# RF2401.net
KiCad netlist of a schematic drawn in Altium Designer
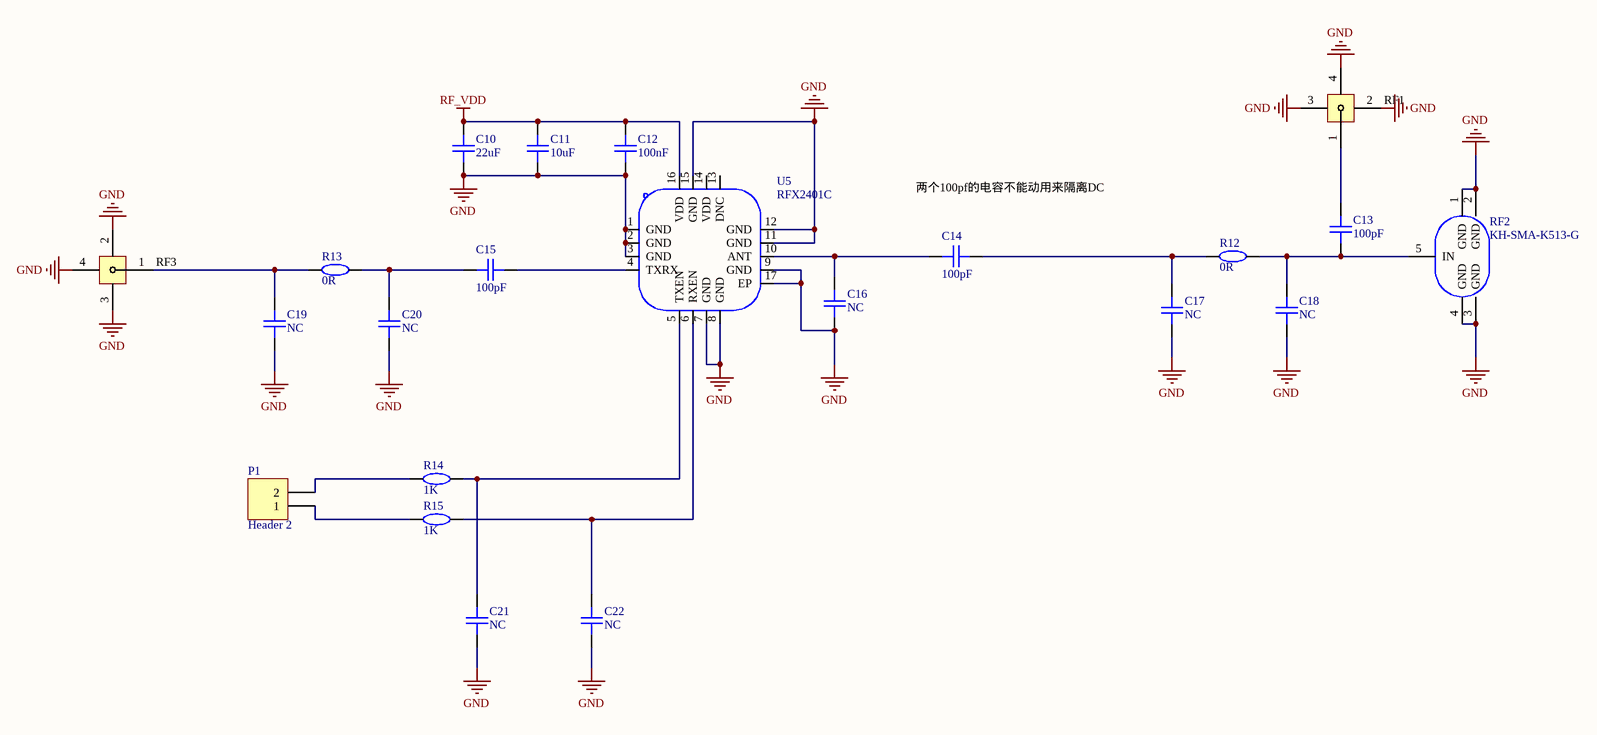
[diagram p0: RF2401.SchDoc]

(export (version "E")
  (design (tool "Eeschema 10.0.6"))
  (components
    (comp (ref "C10")
      (value "22uF")
      (footprint "C0603")
      (fields (field (name "NAME") "22uF"))
      (libsource (lib "my_library") (part "CAP_0603"))
    )
    (comp (ref "C11")
      (value "10uF")
      (footprint "C0603")
      (fields (field (name "NAME") "10uF"))
      (libsource (lib "my_library") (part "CAP_0603"))
    )
    (comp (ref "C12")
      (value "100nF")
      (footprint "C0402")
      (fields (field (name "NAME") "100nF"))
      (libsource (lib "my_library") (part "CAP_0402"))
    )
    (comp (ref "C13")
      (value "100pF")
      (footprint "C0402")
      (fields (field (name "NAME") "100pF"))
      (libsource (lib "my_library") (part "CAP_0402"))
    )
    (comp (ref "C14")
      (value "100pF")
      (footprint "C0402")
      (fields (field (name "NAME") "100pF"))
      (libsource (lib "my_library") (part "CAP_0402"))
    )
    (comp (ref "C15")
      (value "100pF")
      (footprint "C0402")
      (fields (field (name "NAME") "100pF"))
      (libsource (lib "my_library") (part "CAP_0402"))
    )
    (comp (ref "C16")
      (value "NC")
      (footprint "C0402")
      (fields (field (name "NAME") "NC"))
      (libsource (lib "my_library") (part "CAP_0402"))
    )
    (comp (ref "C17")
      (value "NC")
      (footprint "C0402")
      (fields (field (name "NAME") "NC"))
      (libsource (lib "my_library") (part "CAP_0402"))
    )
    (comp (ref "C18")
      (value "NC")
      (footprint "C0402")
      (fields (field (name "NAME") "NC"))
      (libsource (lib "my_library") (part "CAP_0402"))
    )
    (comp (ref "C19")
      (value "NC")
      (footprint "C0402")
      (fields (field (name "NAME") "NC"))
      (libsource (lib "my_library") (part "CAP_0402"))
    )
    (comp (ref "C20")
      (value "NC")
      (footprint "C0402")
      (fields (field (name "NAME") "NC"))
      (libsource (lib "my_library") (part "CAP_0402"))
    )
    (comp (ref "C21")
      (value "NC")
      (footprint "C0402")
      (fields (field (name "NAME") "NC"))
      (libsource (lib "my_library") (part "CAP_0402"))
    )
    (comp (ref "C22")
      (value "NC")
      (footprint "C0402")
      (fields (field (name "NAME") "NC"))
      (libsource (lib "my_library") (part "CAP_0402"))
    )
    (comp (ref "P1")
      (value "Header 2")
      (footprint "HDR1X2")
      (description "Header, 2-Pin")
      (fields (field (name "PUBLISHER") "Altium Limited"))
      (libsource (lib "Miscellaneous Connectors") (part "Header 2"))
    )
    (comp (ref "R12")
      (value "0R")
      (footprint "R0402")
      (fields (field (name "NAME") "0R"))
      (libsource (lib "my_library") (part "Res_0402"))
    )
    (comp (ref "R13")
      (value "0R")
      (footprint "R0402")
      (fields (field (name "NAME") "0R"))
      (libsource (lib "my_library") (part "Res_0402"))
    )
    (comp (ref "R14")
      (value "1K")
      (footprint "R0402")
      (fields (field (name "NAME") "1K"))
      (libsource (lib "my_library") (part "Res_0402"))
    )
    (comp (ref "R15")
      (value "1K")
      (footprint "R0402")
      (fields (field (name "NAME") "1K"))
      (libsource (lib "my_library") (part "Res_0402"))
    )
    (comp (ref "RF1")
      (value "BWIPX-4-001E")
      (footprint "IPEX-SMD_BWIPX-4-001E")
      (description "C784401")
      (fields (field (name "MANUFACTURER") "BAT WIRELESS(蝙蝠无线)"))
      (libsource (lib "my_library") (part "BWIPX-4-001E"))
    )
    (comp (ref "RF2")
      (value "KH-SMA-K513-G")
      (footprint "ANT-TH_KH-SMA-K513-G")
      (fields (field (name "MANUFACTURER") "kinghelm(金航标)") (field (name "NAME") "KH-SMA-K513-G"))
      (libsource (lib "my_library") (part "KH-SMA-K513-G"))
    )
    (comp (ref "RF3")
      (value "BWIPX-4-001E")
      (footprint "IPEX-SMD_BWIPX-4-001E")
      (description "C784401")
      (fields (field (name "MANUFACTURER") "BAT WIRELESS(蝙蝠无线)"))
      (libsource (lib "") (part "BWIPX-4-001E_1"))
    )
    (comp (ref "U5")
      (value "RFX2401C")
      (footprint "QFN-16_L3.0-W3.0-P0.50-BL-EP1.7")
      (fields (field (name "MANUFACTURER") "SKYWORKS") (field (name "NAME") "RFX2401C"))
      (libsource (lib "my_library") (part "RFX2401C"))
    )
  )
  (nets
    (net (code "1") (name "GND") (class "Default")
      (node (ref "C10") (pin "1") (pinfunction "1_1") (pintype "passive"))
      (node (ref "C11") (pin "1") (pinfunction "1_1") (pintype "passive"))
      (node (ref "C12") (pin "1") (pinfunction "1_1") (pintype "passive"))
      (node (ref "C16") (pin "2") (pinfunction "2_2") (pintype "passive"))
      (node (ref "C17") (pin "2") (pinfunction "2_2") (pintype "passive"))
      (node (ref "C18") (pin "2") (pinfunction "2_2") (pintype "passive"))
      (node (ref "C19") (pin "2") (pinfunction "2_2") (pintype "passive"))
      (node (ref "C20") (pin "2") (pinfunction "2_2") (pintype "passive"))
      (node (ref "C21") (pin "2") (pinfunction "2_2") (pintype "passive"))
      (node (ref "C22") (pin "2") (pinfunction "2_2") (pintype "passive"))
      (node (ref "RF1") (pin "2") (pinfunction "2_2") (pintype "passive"))
      (node (ref "RF1") (pin "3") (pinfunction "3_3") (pintype "passive"))
      (node (ref "RF1") (pin "4") (pinfunction "4_4") (pintype "passive"))
      (node (ref "RF2") (pin "1") (pinfunction "GND_1") (pintype "passive"))
      (node (ref "RF2") (pin "2") (pinfunction "GND_2") (pintype "passive"))
      (node (ref "RF2") (pin "3") (pinfunction "GND_3") (pintype "passive"))
      (node (ref "RF2") (pin "4") (pinfunction "GND_4") (pintype "passive"))
      (node (ref "RF3") (pin "2") (pinfunction "2_2") (pintype "passive"))
      (node (ref "RF3") (pin "3") (pinfunction "3_3") (pintype "passive"))
      (node (ref "RF3") (pin "4") (pinfunction "4_4") (pintype "passive"))
      (node (ref "U5") (pin "1") (pinfunction "GND_1") (pintype "passive"))
      (node (ref "U5") (pin "11") (pinfunction "GND_11") (pintype "passive"))
      (node (ref "U5") (pin "12") (pinfunction "GND_12") (pintype "passive"))
      (node (ref "U5") (pin "15") (pinfunction "GND_15") (pintype "passive"))
      (node (ref "U5") (pin "17") (pinfunction "EP_17") (pintype "passive"))
      (node (ref "U5") (pin "2") (pinfunction "GND_2") (pintype "passive"))
      (node (ref "U5") (pin "3") (pinfunction "GND_3") (pintype "passive"))
      (node (ref "U5") (pin "7") (pinfunction "GND_7") (pintype "passive"))
      (node (ref "U5") (pin "8") (pinfunction "GND_8") (pintype "passive"))
      (node (ref "U5") (pin "9") (pinfunction "GND_9") (pintype "passive"))
    )
    (net (code "2") (name "Net-(C13-Pad1)") (class "Default")
      (node (ref "C13") (pin "1") (pinfunction "1_1") (pintype "passive"))
      (node (ref "RF1") (pin "1") (pinfunction "1_1") (pintype "passive"))
    )
    (net (code "3") (name "Net-(C14-Pad1)") (class "Default")
      (node (ref "C14") (pin "1") (pinfunction "1_1") (pintype "passive"))
      (node (ref "C17") (pin "1") (pinfunction "1_1") (pintype "passive"))
      (node (ref "R12") (pin "1") (pinfunction "1_1") (pintype "passive"))
    )
    (net (code "4") (name "Net-(C15-Pad2)") (class "Default")
      (node (ref "C15") (pin "2") (pinfunction "2_2") (pintype "passive"))
      (node (ref "C20") (pin "1") (pinfunction "1_1") (pintype "passive"))
      (node (ref "R13") (pin "2") (pinfunction "2_2") (pintype "passive"))
    )
    (net (code "5") (name "Net-(C19-Pad1)") (class "Default")
      (node (ref "C19") (pin "1") (pinfunction "1_1") (pintype "passive"))
      (node (ref "R13") (pin "1") (pinfunction "1_1") (pintype "passive"))
      (node (ref "RF3") (pin "1") (pinfunction "1_1") (pintype "passive"))
    )
    (net (code "6") (name "Net-(P1-Pad1)") (class "Default")
      (node (ref "P1") (pin "1") (pinfunction "1_1") (pintype "passive"))
      (node (ref "R15") (pin "1") (pinfunction "1_1") (pintype "passive"))
    )
    (net (code "7") (name "Net-(P1-Pad2)") (class "Default")
      (node (ref "P1") (pin "2") (pinfunction "2_2") (pintype "passive"))
      (node (ref "R14") (pin "1") (pinfunction "1_1") (pintype "passive"))
    )
    (net (code "8") (name "Net-(RF2-IN)") (class "Default")
      (node (ref "C13") (pin "2") (pinfunction "2_2") (pintype "passive"))
      (node (ref "C18") (pin "1") (pinfunction "1_1") (pintype "passive"))
      (node (ref "R12") (pin "2") (pinfunction "2_2") (pintype "passive"))
      (node (ref "RF2") (pin "5") (pinfunction "IN_5") (pintype "passive"))
    )
    (net (code "9") (name "Net-(U5-ANT)") (class "Default")
      (node (ref "C14") (pin "2") (pinfunction "2_2") (pintype "passive"))
      (node (ref "C16") (pin "1") (pinfunction "1_1") (pintype "passive"))
      (node (ref "U5") (pin "10") (pinfunction "ANT_10") (pintype "passive"))
    )
    (net (code "10") (name "Net-(U5-RXEN)") (class "Default")
      (node (ref "C22") (pin "1") (pinfunction "1_1") (pintype "passive"))
      (node (ref "R15") (pin "2") (pinfunction "2_2") (pintype "passive"))
      (node (ref "U5") (pin "6") (pinfunction "RXEN_6") (pintype "passive"))
    )
    (net (code "11") (name "Net-(U5-TXEN)") (class "Default")
      (node (ref "C21") (pin "1") (pinfunction "1_1") (pintype "passive"))
      (node (ref "R14") (pin "2") (pinfunction "2_2") (pintype "passive"))
      (node (ref "U5") (pin "5") (pinfunction "TXEN_5") (pintype "passive"))
    )
    (net (code "12") (name "Net-(U5-TXRX)") (class "Default")
      (node (ref "C15") (pin "1") (pinfunction "1_1") (pintype "passive"))
      (node (ref "U5") (pin "4") (pinfunction "TXRX_4") (pintype "passive"))
    )
    (net (code "13") (name "RF_VDD") (class "Default")
      (node (ref "C10") (pin "2") (pinfunction "2_2") (pintype "passive"))
      (node (ref "C11") (pin "2") (pinfunction "2_2") (pintype "passive"))
      (node (ref "C12") (pin "2") (pinfunction "2_2") (pintype "passive"))
      (node (ref "U5") (pin "16") (pinfunction "VDD_16") (pintype "passive"))
    )
    (net (code "14") (name "unconnected-(U5-DNC-Pad13)") (class "Default")
      (node (ref "U5") (pin "13") (pinfunction "DNC_13") (pintype "passive"))
    )
    (net (code "15") (name "unconnected-(U5-VDD-Pad14)") (class "Default")
      (node (ref "U5") (pin "14") (pinfunction "VDD_14") (pintype "passive"))
    )
  )
)
